# Robot_HC-SR04v1.net
KiCad netlist of a schematic drawn in EAGLE
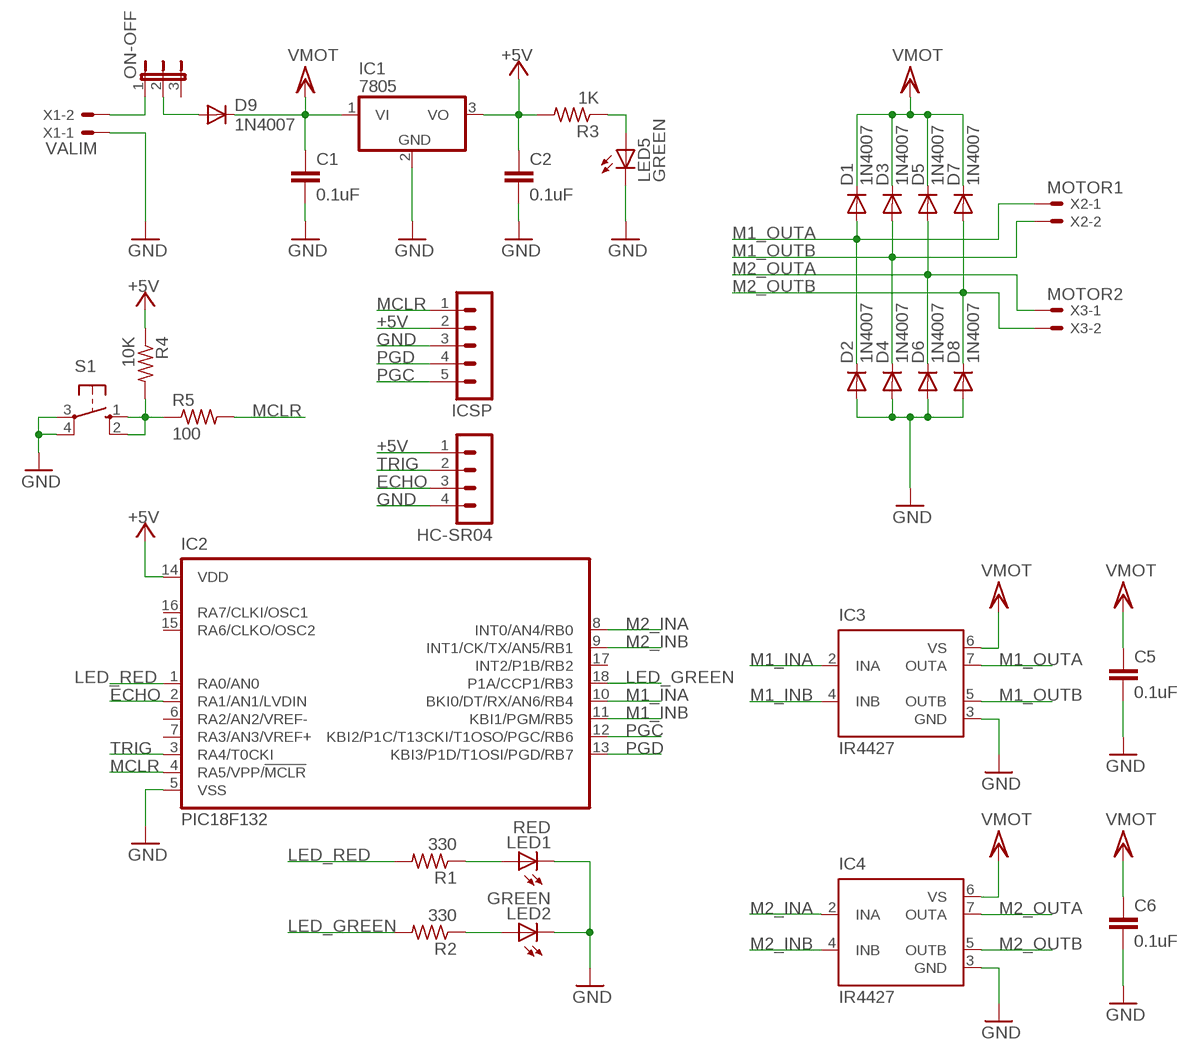
[diagram p0: schematic, sheet 1]

(export (version "E")
  (design (tool "Eeschema 10.0.6"))
  (components
    (comp (ref "C1")
      (value "0.1uF")
      (footprint "eagle-import:C050-024X044")
      (libsource (lib "eagle-import") (part "C-EU050-024X044"))
    )
    (comp (ref "C2")
      (value "0.1uF")
      (footprint "eagle-import:C050-024X044")
      (libsource (lib "eagle-import") (part "C-EU050-024X044"))
    )
    (comp (ref "C5")
      (value "0.1uF")
      (footprint "eagle-import:C050-024X044")
      (libsource (lib "eagle-import") (part "C-EU050-024X044"))
    )
    (comp (ref "C6")
      (value "0.1uF")
      (footprint "eagle-import:C050-024X044")
      (libsource (lib "eagle-import") (part "C-EU050-024X044"))
    )
    (comp (ref "D1")
      (value "1N4007")
      (footprint "eagle-import:DO41-10")
      (libsource (lib "eagle-import") (part "1N4004"))
    )
    (comp (ref "D2")
      (value "1N4007")
      (footprint "eagle-import:DO41-10")
      (libsource (lib "eagle-import") (part "1N4004"))
    )
    (comp (ref "D3")
      (value "1N4007")
      (footprint "eagle-import:DO41-10")
      (libsource (lib "eagle-import") (part "1N4004"))
    )
    (comp (ref "D4")
      (value "1N4007")
      (footprint "eagle-import:DO41-10")
      (libsource (lib "eagle-import") (part "1N4004"))
    )
    (comp (ref "D5")
      (value "1N4007")
      (footprint "eagle-import:DO41-10")
      (libsource (lib "eagle-import") (part "1N4004"))
    )
    (comp (ref "D6")
      (value "1N4007")
      (footprint "eagle-import:DO41-10")
      (libsource (lib "eagle-import") (part "1N4004"))
    )
    (comp (ref "D7")
      (value "1N4007")
      (footprint "eagle-import:DO41-10")
      (libsource (lib "eagle-import") (part "1N4004"))
    )
    (comp (ref "D8")
      (value "1N4007")
      (footprint "eagle-import:DO41-10")
      (libsource (lib "eagle-import") (part "1N4004"))
    )
    (comp (ref "D9")
      (value "1N4007")
      (footprint "eagle-import:DO41-10")
      (libsource (lib "eagle-import") (part "1N4004"))
    )
    (comp (ref "HC-SR04")
      (value "MA04-1")
      (footprint "eagle-import:MA04-1")
      (libsource (lib "eagle-import") (part "MA04-1"))
    )
    (comp (ref "IC1")
      (value "7805")
      (footprint "eagle-import:TO220H")
      (libsource (lib "eagle-import") (part "78T05"))
    )
    (comp (ref "IC2")
      (value "PIC18F132")
      (footprint "eagle-import:SO-18W")
      (libsource (lib "eagle-import") (part "PIC18F1320SO"))
    )
    (comp (ref "IC3")
      (value "IR4427")
      (footprint "eagle-import:DIL08")
      (libsource (lib "eagle-import") (part "IR4427"))
    )
    (comp (ref "IC4")
      (value "IR4427")
      (footprint "eagle-import:DIL08")
      (libsource (lib "eagle-import") (part "IR4427"))
    )
    (comp (ref "ICSP")
      (value "MA05-1")
      (footprint "eagle-import:MA05-1")
      (libsource (lib "eagle-import") (part "MA05-1"))
    )
    (comp (ref "LED1")
      (value "RED")
      (footprint "eagle-import:LED3MM")
      (libsource (lib "eagle-import") (part "LED3MM"))
    )
    (comp (ref "LED2")
      (value "GREEN")
      (footprint "eagle-import:LED3MM")
      (libsource (lib "eagle-import") (part "LED3MM"))
    )
    (comp (ref "LED5")
      (value "GREEN")
      (footprint "eagle-import:LED3MM")
      (libsource (lib "eagle-import") (part "LED3MM"))
    )
    (comp (ref "ON-OFF")
      (value "JP2E")
      (footprint "eagle-import:JP2")
      (libsource (lib "eagle-import") (part "JP2E"))
    )
    (comp (ref "R1")
      (value "330")
      (footprint "eagle-import:0207_7")
      (libsource (lib "eagle-import") (part "R-US_0207/7"))
    )
    (comp (ref "R2")
      (value "330")
      (footprint "eagle-import:0207_7")
      (libsource (lib "eagle-import") (part "R-US_0207/7"))
    )
    (comp (ref "R3")
      (value "1K")
      (footprint "eagle-import:0207_7")
      (libsource (lib "eagle-import") (part "R-US_0207/7"))
    )
    (comp (ref "R4")
      (value "10K")
      (footprint "eagle-import:0207_7")
      (libsource (lib "eagle-import") (part "R-US_0207/7"))
    )
    (comp (ref "R5")
      (value "100")
      (footprint "eagle-import:0207_7")
      (libsource (lib "eagle-import") (part "R-US_0207/7"))
    )
    (comp (ref "S1")
      (value "10-XX")
      (footprint "eagle-import:B3F-10XX")
      (fields (field (name "MPN") "B3F-1000"))
      (libsource (lib "eagle-import") (part "10-XX"))
    )
    (comp (ref "X1")
      (value "VALIM")
      (footprint "eagle-import:22-23-2021")
      (fields (field (name "MF") "MOLEX") (field (name "MPN") "22-23-2021"))
      (libsource (lib "eagle-import") (part "22-23-2021"))
    )
    (comp (ref "X2")
      (value "MOTOR1")
      (footprint "eagle-import:22-23-2021")
      (fields (field (name "MF") "MOLEX") (field (name "MPN") "22-23-2021"))
      (libsource (lib "eagle-import") (part "22-23-2021"))
    )
    (comp (ref "X3")
      (value "MOTOR2")
      (footprint "eagle-import:22-23-2021")
      (fields (field (name "MF") "MOLEX") (field (name "MPN") "22-23-2021"))
      (libsource (lib "eagle-import") (part "22-23-2021"))
    )
  )
  (nets
    (net (code "1") (name "+5V") (class "Default")
      (node (ref "C2") (pin "1") (pinfunction "1_1") (pintype "passive"))
      (node (ref "HC-SR04") (pin "1") (pinfunction "1_1") (pintype "passive"))
      (node (ref "IC1") (pin "3") (pinfunction "VO_3") (pintype "passive"))
      (node (ref "IC2") (pin "14") (pinfunction "VDD_14") (pintype "power_in"))
      (node (ref "ICSP") (pin "2") (pinfunction "2_2") (pintype "passive"))
      (node (ref "R3") (pin "2") (pinfunction "2_2") (pintype "passive"))
      (node (ref "R4") (pin "1") (pinfunction "1_1") (pintype "passive"))
    )
    (net (code "2") (name "/ECHO") (class "Default")
      (node (ref "HC-SR04") (pin "3") (pinfunction "3_3") (pintype "passive"))
      (node (ref "IC2") (pin "2") (pinfunction "RA1/AN1/LVDIN_2") (pintype "bidirectional"))
    )
    (net (code "3") (name "/LED_GREEN") (class "Default")
      (node (ref "IC2") (pin "18") (pinfunction "P1A/CCP1/RB3_18") (pintype "bidirectional"))
      (node (ref "R2") (pin "2") (pinfunction "2_2") (pintype "passive"))
    )
    (net (code "4") (name "/LED_RED") (class "Default")
      (node (ref "IC2") (pin "1") (pinfunction "RA0/AN0_1") (pintype "bidirectional"))
      (node (ref "R1") (pin "2") (pinfunction "2_2") (pintype "passive"))
    )
    (net (code "5") (name "/M1_INA") (class "Default")
      (node (ref "IC2") (pin "10") (pinfunction "BKI0/DT/RX/AN6/RB4_10") (pintype "bidirectional"))
      (node (ref "IC3") (pin "2") (pinfunction "INA_2") (pintype "input"))
    )
    (net (code "6") (name "/M1_INB") (class "Default")
      (node (ref "IC2") (pin "11") (pinfunction "KBI1/PGM/RB5_11") (pintype "bidirectional"))
      (node (ref "IC3") (pin "4") (pinfunction "INB_4") (pintype "input"))
    )
    (net (code "7") (name "/M1_OUTA") (class "Default")
      (node (ref "D1") (pin "A") (pinfunction "A_A") (pintype "passive"))
      (node (ref "D2") (pin "C") (pinfunction "C_C") (pintype "passive"))
      (node (ref "IC3") (pin "7") (pinfunction "OUTA_7") (pintype "output"))
      (node (ref "X2") (pin "1") (pinfunction "S_1") (pintype "passive"))
    )
    (net (code "8") (name "/M1_OUTB") (class "Default")
      (node (ref "D3") (pin "A") (pinfunction "A_A") (pintype "passive"))
      (node (ref "D4") (pin "C") (pinfunction "C_C") (pintype "passive"))
      (node (ref "IC3") (pin "5") (pinfunction "OUTB_5") (pintype "output"))
      (node (ref "X2") (pin "2") (pinfunction "S_2") (pintype "passive"))
    )
    (net (code "9") (name "/M2_INA") (class "Default")
      (node (ref "IC2") (pin "8") (pinfunction "INT0/AN4/RB0_8") (pintype "bidirectional"))
      (node (ref "IC4") (pin "2") (pinfunction "INA_2") (pintype "input"))
    )
    (net (code "10") (name "/M2_INB") (class "Default")
      (node (ref "IC2") (pin "9") (pinfunction "INT1/CK/TX/AN5/RB1_9") (pintype "bidirectional"))
      (node (ref "IC4") (pin "4") (pinfunction "INB_4") (pintype "input"))
    )
    (net (code "11") (name "/M2_OUTA") (class "Default")
      (node (ref "D5") (pin "A") (pinfunction "A_A") (pintype "passive"))
      (node (ref "D6") (pin "C") (pinfunction "C_C") (pintype "passive"))
      (node (ref "IC4") (pin "7") (pinfunction "OUTA_7") (pintype "output"))
      (node (ref "X3") (pin "1") (pinfunction "S_1") (pintype "passive"))
    )
    (net (code "12") (name "/M2_OUTB") (class "Default")
      (node (ref "D7") (pin "A") (pinfunction "A_A") (pintype "passive"))
      (node (ref "D8") (pin "C") (pinfunction "C_C") (pintype "passive"))
      (node (ref "IC4") (pin "5") (pinfunction "OUTB_5") (pintype "output"))
      (node (ref "X3") (pin "2") (pinfunction "S_2") (pintype "passive"))
    )
    (net (code "13") (name "/MCLR") (class "Default")
      (node (ref "IC2") (pin "4") (pinfunction "RA5/VPP/~{MCLR}_4") (pintype "input"))
      (node (ref "ICSP") (pin "1") (pinfunction "1_1") (pintype "passive"))
      (node (ref "R5") (pin "2") (pinfunction "2_2") (pintype "passive"))
    )
    (net (code "14") (name "/PGC") (class "Default")
      (node (ref "IC2") (pin "12") (pinfunction "KBI2/P1C/T13CKI/T1OSO/PGC/RB6_12") (pintype "bidirectional"))
      (node (ref "ICSP") (pin "5") (pinfunction "5_5") (pintype "passive"))
    )
    (net (code "15") (name "/PGD") (class "Default")
      (node (ref "IC2") (pin "13") (pinfunction "KBI3/P1D/T1OSI/PGD/RB7_13") (pintype "bidirectional"))
      (node (ref "ICSP") (pin "4") (pinfunction "4_4") (pintype "passive"))
    )
    (net (code "16") (name "/TRIG") (class "Default")
      (node (ref "HC-SR04") (pin "2") (pinfunction "2_2") (pintype "passive"))
      (node (ref "IC2") (pin "3") (pinfunction "RA4/T0CKI_3") (pintype "bidirectional"))
    )
    (net (code "17") (name "GND") (class "Default")
      (node (ref "C1") (pin "2") (pinfunction "2_2") (pintype "passive"))
      (node (ref "C2") (pin "2") (pinfunction "2_2") (pintype "passive"))
      (node (ref "C5") (pin "2") (pinfunction "2_2") (pintype "passive"))
      (node (ref "C6") (pin "2") (pinfunction "2_2") (pintype "passive"))
      (node (ref "D2") (pin "A") (pinfunction "A_A") (pintype "passive"))
      (node (ref "D4") (pin "A") (pinfunction "A_A") (pintype "passive"))
      (node (ref "D6") (pin "A") (pinfunction "A_A") (pintype "passive"))
      (node (ref "D8") (pin "A") (pinfunction "A_A") (pintype "passive"))
      (node (ref "HC-SR04") (pin "4") (pinfunction "4_4") (pintype "passive"))
      (node (ref "IC1") (pin "2") (pinfunction "GND_2") (pintype "passive"))
      (node (ref "IC2") (pin "5") (pinfunction "VSS_5") (pintype "power_in"))
      (node (ref "IC3") (pin "3") (pinfunction "GND_3") (pintype "power_in"))
      (node (ref "IC4") (pin "3") (pinfunction "GND_3") (pintype "power_in"))
      (node (ref "ICSP") (pin "3") (pinfunction "3_3") (pintype "passive"))
      (node (ref "LED1") (pin "K") (pinfunction "C_K") (pintype "passive"))
      (node (ref "LED2") (pin "K") (pinfunction "C_K") (pintype "passive"))
      (node (ref "LED5") (pin "K") (pinfunction "C_K") (pintype "passive"))
      (node (ref "S1") (pin "3") (pinfunction "P_3") (pintype "passive"))
      (node (ref "S1") (pin "4") (pinfunction "P1_4") (pintype "passive"))
      (node (ref "X1") (pin "1") (pinfunction "S_1") (pintype "passive"))
    )
    (net (code "18") (name "Net-(D9-PadA)") (class "Default")
      (node (ref "D9") (pin "A") (pinfunction "A_A") (pintype "passive"))
      (node (ref "ON-OFF") (pin "2") (pinfunction "2_2") (pintype "passive"))
    )
    (net (code "19") (name "Net-(LED1-PadA)") (class "Default")
      (node (ref "LED1") (pin "A") (pinfunction "A_A") (pintype "passive"))
      (node (ref "R1") (pin "1") (pinfunction "1_1") (pintype "passive"))
    )
    (net (code "20") (name "Net-(LED2-PadA)") (class "Default")
      (node (ref "LED2") (pin "A") (pinfunction "A_A") (pintype "passive"))
      (node (ref "R2") (pin "1") (pinfunction "1_1") (pintype "passive"))
    )
    (net (code "21") (name "Net-(LED5-PadA)") (class "Default")
      (node (ref "LED5") (pin "A") (pinfunction "A_A") (pintype "passive"))
      (node (ref "R3") (pin "1") (pinfunction "1_1") (pintype "passive"))
    )
    (net (code "22") (name "Net-(S1-S)") (class "Default")
      (node (ref "R4") (pin "2") (pinfunction "2_2") (pintype "passive"))
      (node (ref "R5") (pin "1") (pinfunction "1_1") (pintype "passive"))
      (node (ref "S1") (pin "1") (pinfunction "S_1") (pintype "passive"))
      (node (ref "S1") (pin "2") (pinfunction "S1_2") (pintype "passive"))
    )
    (net (code "23") (name "Net-(X1B-S)") (class "Default")
      (node (ref "ON-OFF") (pin "1") (pinfunction "1_1") (pintype "passive"))
      (node (ref "X1") (pin "2") (pinfunction "S_2") (pintype "passive"))
    )
    (net (code "24") (name "VMOT") (class "Default")
      (node (ref "C1") (pin "1") (pinfunction "1_1") (pintype "passive"))
      (node (ref "C5") (pin "1") (pinfunction "1_1") (pintype "passive"))
      (node (ref "C6") (pin "1") (pinfunction "1_1") (pintype "passive"))
      (node (ref "D1") (pin "C") (pinfunction "C_C") (pintype "passive"))
      (node (ref "D3") (pin "C") (pinfunction "C_C") (pintype "passive"))
      (node (ref "D5") (pin "C") (pinfunction "C_C") (pintype "passive"))
      (node (ref "D7") (pin "C") (pinfunction "C_C") (pintype "passive"))
      (node (ref "D9") (pin "C") (pinfunction "C_C") (pintype "passive"))
      (node (ref "IC1") (pin "1") (pinfunction "VI_1") (pintype "input"))
      (node (ref "IC3") (pin "6") (pinfunction "VS_6") (pintype "power_in"))
      (node (ref "IC4") (pin "6") (pinfunction "VS_6") (pintype "power_in"))
    )
    (net (code "25") (name "unconnected-(IC2-INT2{slash}P1B{slash}RB2-Pad17)") (class "Default")
      (node (ref "IC2") (pin "17") (pinfunction "INT2/P1B/RB2_17") (pintype "bidirectional"))
    )
    (net (code "26") (name "unconnected-(IC2-RA2{slash}AN2{slash}VREF--Pad6)") (class "Default")
      (node (ref "IC2") (pin "6") (pinfunction "RA2/AN2/VREF-_6") (pintype "bidirectional"))
    )
    (net (code "27") (name "unconnected-(IC2-RA3{slash}AN3{slash}VREF+-Pad7)") (class "Default")
      (node (ref "IC2") (pin "7") (pinfunction "RA3/AN3/VREF+_7") (pintype "bidirectional"))
    )
    (net (code "28") (name "unconnected-(IC2-RA6{slash}CLKO{slash}OSC2-Pad15)") (class "Default")
      (node (ref "IC2") (pin "15") (pinfunction "RA6/CLKO/OSC2_15") (pintype "bidirectional"))
    )
    (net (code "29") (name "unconnected-(IC2-RA7{slash}CLKI{slash}OSC1-Pad16)") (class "Default")
      (node (ref "IC2") (pin "16") (pinfunction "RA7/CLKI/OSC1_16") (pintype "bidirectional"))
    )
    (net (code "30") (name "unconnected-(ON-OFF-Pad3)") (class "Default")
      (node (ref "ON-OFF") (pin "3") (pinfunction "3_3") (pintype "passive"))
    )
  )
)
